# lamp.net
KiCad netlist of a schematic drawn in EAGLE
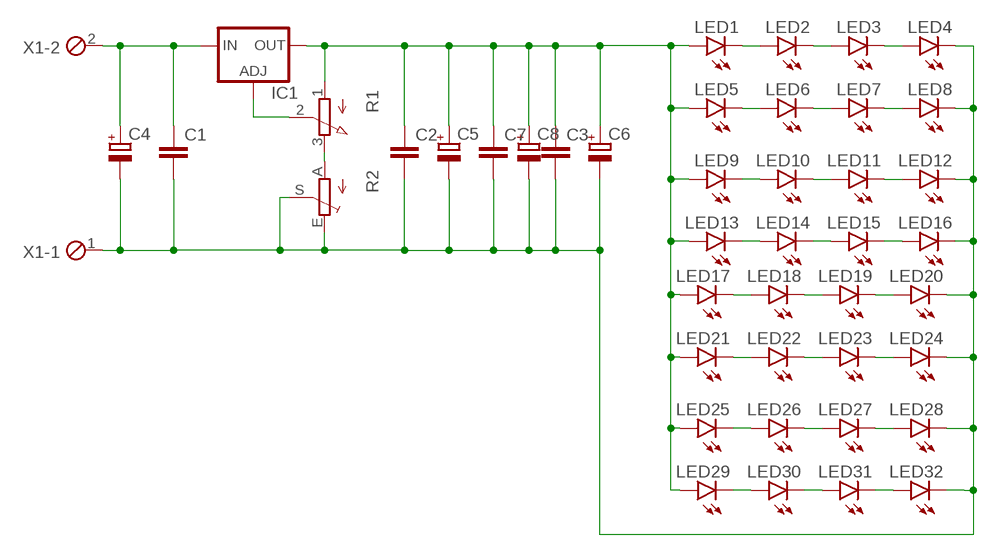
[diagram p0: schematic, sheet 1]

(export (version "E")
  (design (tool "Eeschema 10.0.6"))
  (components
    (comp (ref "C1")
      (value "C-EU025-025X050")
      (footprint "eagle-import:C025-025X050")
      (libsource (lib "eagle-import") (part "C-EU025-025X050"))
    )
    (comp (ref "C2")
      (value "C-EU025-025X050")
      (footprint "eagle-import:C025-025X050")
      (libsource (lib "eagle-import") (part "C-EU025-025X050"))
    )
    (comp (ref "C3")
      (value "C-EU025-025X050")
      (footprint "eagle-import:C025-025X050")
      (libsource (lib "eagle-import") (part "C-EU025-025X050"))
    )
    (comp (ref "C4")
      (value "CPOL-EUE2-5")
      (footprint "eagle-import:E2-5")
      (libsource (lib "eagle-import") (part "CPOL-EUE2-5"))
    )
    (comp (ref "C5")
      (value "CPOL-EUE2-5")
      (footprint "eagle-import:E2-5")
      (libsource (lib "eagle-import") (part "CPOL-EUE2-5"))
    )
    (comp (ref "C6")
      (value "CPOL-EUE2-5")
      (footprint "eagle-import:E2-5")
      (libsource (lib "eagle-import") (part "CPOL-EUE2-5"))
    )
    (comp (ref "C7")
      (value "C-EU025-025X050")
      (footprint "eagle-import:C025-025X050")
      (libsource (lib "eagle-import") (part "C-EU025-025X050"))
    )
    (comp (ref "C8")
      (value "CPOL-EUE2-5")
      (footprint "eagle-import:E2-5")
      (libsource (lib "eagle-import") (part "CPOL-EUE2-5"))
    )
    (comp (ref "IC1")
      (value "LM317TS")
      (footprint "eagle-import:317TS")
      (libsource (lib "eagle-import") (part "LM317TS"))
    )
    (comp (ref "LED1")
      (value "LED3MM")
      (footprint "eagle-import:LED3MM")
      (libsource (lib "eagle-import") (part "LED3MM"))
    )
    (comp (ref "LED2")
      (value "LED3MM")
      (footprint "eagle-import:LED3MM")
      (libsource (lib "eagle-import") (part "LED3MM"))
    )
    (comp (ref "LED3")
      (value "LED3MM")
      (footprint "eagle-import:LED3MM")
      (libsource (lib "eagle-import") (part "LED3MM"))
    )
    (comp (ref "LED4")
      (value "LED3MM")
      (footprint "eagle-import:LED3MM")
      (libsource (lib "eagle-import") (part "LED3MM"))
    )
    (comp (ref "LED5")
      (value "LED3MM")
      (footprint "eagle-import:LED3MM")
      (libsource (lib "eagle-import") (part "LED3MM"))
    )
    (comp (ref "LED6")
      (value "LED3MM")
      (footprint "eagle-import:LED3MM")
      (libsource (lib "eagle-import") (part "LED3MM"))
    )
    (comp (ref "LED7")
      (value "LED3MM")
      (footprint "eagle-import:LED3MM")
      (libsource (lib "eagle-import") (part "LED3MM"))
    )
    (comp (ref "LED8")
      (value "LED3MM")
      (footprint "eagle-import:LED3MM")
      (libsource (lib "eagle-import") (part "LED3MM"))
    )
    (comp (ref "LED9")
      (value "LED3MM")
      (footprint "eagle-import:LED3MM")
      (libsource (lib "eagle-import") (part "LED3MM"))
    )
    (comp (ref "LED10")
      (value "LED3MM")
      (footprint "eagle-import:LED3MM")
      (libsource (lib "eagle-import") (part "LED3MM"))
    )
    (comp (ref "LED11")
      (value "LED3MM")
      (footprint "eagle-import:LED3MM")
      (libsource (lib "eagle-import") (part "LED3MM"))
    )
    (comp (ref "LED12")
      (value "LED3MM")
      (footprint "eagle-import:LED3MM")
      (libsource (lib "eagle-import") (part "LED3MM"))
    )
    (comp (ref "LED13")
      (value "LED3MM")
      (footprint "eagle-import:LED3MM")
      (libsource (lib "eagle-import") (part "LED3MM"))
    )
    (comp (ref "LED14")
      (value "LED3MM")
      (footprint "eagle-import:LED3MM")
      (libsource (lib "eagle-import") (part "LED3MM"))
    )
    (comp (ref "LED15")
      (value "LED3MM")
      (footprint "eagle-import:LED3MM")
      (libsource (lib "eagle-import") (part "LED3MM"))
    )
    (comp (ref "LED16")
      (value "LED3MM")
      (footprint "eagle-import:LED3MM")
      (libsource (lib "eagle-import") (part "LED3MM"))
    )
    (comp (ref "LED17")
      (value "LED3MM")
      (footprint "eagle-import:LED3MM")
      (libsource (lib "eagle-import") (part "LED3MM"))
    )
    (comp (ref "LED18")
      (value "LED3MM")
      (footprint "eagle-import:LED3MM")
      (libsource (lib "eagle-import") (part "LED3MM"))
    )
    (comp (ref "LED19")
      (value "LED3MM")
      (footprint "eagle-import:LED3MM")
      (libsource (lib "eagle-import") (part "LED3MM"))
    )
    (comp (ref "LED20")
      (value "LED3MM")
      (footprint "eagle-import:LED3MM")
      (libsource (lib "eagle-import") (part "LED3MM"))
    )
    (comp (ref "LED21")
      (value "LED3MM")
      (footprint "eagle-import:LED3MM")
      (libsource (lib "eagle-import") (part "LED3MM"))
    )
    (comp (ref "LED22")
      (value "LED3MM")
      (footprint "eagle-import:LED3MM")
      (libsource (lib "eagle-import") (part "LED3MM"))
    )
    (comp (ref "LED23")
      (value "LED3MM")
      (footprint "eagle-import:LED3MM")
      (libsource (lib "eagle-import") (part "LED3MM"))
    )
    (comp (ref "LED24")
      (value "LED3MM")
      (footprint "eagle-import:LED3MM")
      (libsource (lib "eagle-import") (part "LED3MM"))
    )
    (comp (ref "LED25")
      (value "LED3MM")
      (footprint "eagle-import:LED3MM")
      (libsource (lib "eagle-import") (part "LED3MM"))
    )
    (comp (ref "LED26")
      (value "LED3MM")
      (footprint "eagle-import:LED3MM")
      (libsource (lib "eagle-import") (part "LED3MM"))
    )
    (comp (ref "LED27")
      (value "LED3MM")
      (footprint "eagle-import:LED3MM")
      (libsource (lib "eagle-import") (part "LED3MM"))
    )
    (comp (ref "LED28")
      (value "LED3MM")
      (footprint "eagle-import:LED3MM")
      (libsource (lib "eagle-import") (part "LED3MM"))
    )
    (comp (ref "LED29")
      (value "LED3MM")
      (footprint "eagle-import:LED3MM")
      (libsource (lib "eagle-import") (part "LED3MM"))
    )
    (comp (ref "LED30")
      (value "LED3MM")
      (footprint "eagle-import:LED3MM")
      (libsource (lib "eagle-import") (part "LED3MM"))
    )
    (comp (ref "LED31")
      (value "LED3MM")
      (footprint "eagle-import:LED3MM")
      (libsource (lib "eagle-import") (part "LED3MM"))
    )
    (comp (ref "LED32")
      (value "LED3MM")
      (footprint "eagle-import:LED3MM")
      (libsource (lib "eagle-import") (part "LED3MM"))
    )
    (comp (ref "R1")
      (value "3RP/1610N")
      (footprint "eagle-import:3RP_1610N")
      (libsource (lib "eagle-import") (part "3RP/1610N"))
    )
    (comp (ref "R2")
      (value "TRIM_EU-CA6V")
      (footprint "eagle-import:CA6V")
      (libsource (lib "eagle-import") (part "TRIM_EU-CA6V"))
    )
    (comp (ref "X1")
      (value "MPT2")
      (footprint "eagle-import:2POL254")
      (libsource (lib "eagle-import") (part "MPT2"))
    )
  )
  (nets
    (net (code "1") (name "Net-(IC1-ADJ)") (class "Default")
      (node (ref "IC1") (pin "1") (pinfunction "ADJ_1") (pintype "input"))
      (node (ref "R1") (pin "2") (pinfunction "S_2") (pintype "passive"))
    )
    (net (code "2") (name "Net-(IC1-IN)") (class "Default")
      (node (ref "C1") (pin "1") (pinfunction "1_1") (pintype "passive"))
      (node (ref "C4") (pin "+") (pinfunction "+_+") (pintype "passive"))
      (node (ref "IC1") (pin "3") (pinfunction "IN_3") (pintype "input"))
      (node (ref "X1") (pin "2") (pinfunction "1_2") (pintype "passive"))
    )
    (net (code "3") (name "Net-(IC1-OUT)") (class "Default")
      (node (ref "C2") (pin "1") (pinfunction "1_1") (pintype "passive"))
      (node (ref "C3") (pin "1") (pinfunction "1_1") (pintype "passive"))
      (node (ref "C5") (pin "+") (pinfunction "+_+") (pintype "passive"))
      (node (ref "C6") (pin "+") (pinfunction "+_+") (pintype "passive"))
      (node (ref "C7") (pin "1") (pinfunction "1_1") (pintype "passive"))
      (node (ref "C8") (pin "+") (pinfunction "+_+") (pintype "passive"))
      (node (ref "IC1") (pin "2") (pinfunction "OUT_2") (pintype "passive"))
      (node (ref "LED1") (pin "A") (pinfunction "A_A") (pintype "passive"))
      (node (ref "LED13") (pin "A") (pinfunction "A_A") (pintype "passive"))
      (node (ref "LED17") (pin "A") (pinfunction "A_A") (pintype "passive"))
      (node (ref "LED21") (pin "A") (pinfunction "A_A") (pintype "passive"))
      (node (ref "LED25") (pin "A") (pinfunction "A_A") (pintype "passive"))
      (node (ref "LED29") (pin "A") (pinfunction "A_A") (pintype "passive"))
      (node (ref "LED5") (pin "A") (pinfunction "A_A") (pintype "passive"))
      (node (ref "LED9") (pin "A") (pinfunction "A_A") (pintype "passive"))
      (node (ref "R1") (pin "1") (pinfunction "A_1") (pintype "passive"))
    )
    (net (code "4") (name "Net-(LED1-C)") (class "Default")
      (node (ref "LED1") (pin "K") (pinfunction "C_K") (pintype "passive"))
      (node (ref "LED2") (pin "A") (pinfunction "A_A") (pintype "passive"))
    )
    (net (code "5") (name "Net-(LED2-C)") (class "Default")
      (node (ref "LED2") (pin "K") (pinfunction "C_K") (pintype "passive"))
      (node (ref "LED3") (pin "A") (pinfunction "A_A") (pintype "passive"))
    )
    (net (code "6") (name "Net-(LED3-C)") (class "Default")
      (node (ref "LED3") (pin "K") (pinfunction "C_K") (pintype "passive"))
      (node (ref "LED4") (pin "A") (pinfunction "A_A") (pintype "passive"))
    )
    (net (code "7") (name "Net-(LED5-C)") (class "Default")
      (node (ref "LED5") (pin "K") (pinfunction "C_K") (pintype "passive"))
      (node (ref "LED6") (pin "A") (pinfunction "A_A") (pintype "passive"))
    )
    (net (code "8") (name "Net-(LED6-C)") (class "Default")
      (node (ref "LED6") (pin "K") (pinfunction "C_K") (pintype "passive"))
      (node (ref "LED7") (pin "A") (pinfunction "A_A") (pintype "passive"))
    )
    (net (code "9") (name "Net-(LED7-C)") (class "Default")
      (node (ref "LED7") (pin "K") (pinfunction "C_K") (pintype "passive"))
      (node (ref "LED8") (pin "A") (pinfunction "A_A") (pintype "passive"))
    )
    (net (code "10") (name "Net-(LED9-C)") (class "Default")
      (node (ref "LED10") (pin "A") (pinfunction "A_A") (pintype "passive"))
      (node (ref "LED9") (pin "K") (pinfunction "C_K") (pintype "passive"))
    )
    (net (code "11") (name "Net-(LED10-C)") (class "Default")
      (node (ref "LED10") (pin "K") (pinfunction "C_K") (pintype "passive"))
      (node (ref "LED11") (pin "A") (pinfunction "A_A") (pintype "passive"))
    )
    (net (code "12") (name "Net-(LED11-C)") (class "Default")
      (node (ref "LED11") (pin "K") (pinfunction "C_K") (pintype "passive"))
      (node (ref "LED12") (pin "A") (pinfunction "A_A") (pintype "passive"))
    )
    (net (code "13") (name "Net-(LED12-C)") (class "Default")
      (node (ref "C1") (pin "2") (pinfunction "2_2") (pintype "passive"))
      (node (ref "C2") (pin "2") (pinfunction "2_2") (pintype "passive"))
      (node (ref "C3") (pin "2") (pinfunction "2_2") (pintype "passive"))
      (node (ref "C4") (pin "-") (pinfunction "-_-") (pintype "passive"))
      (node (ref "C5") (pin "-") (pinfunction "-_-") (pintype "passive"))
      (node (ref "C6") (pin "-") (pinfunction "-_-") (pintype "passive"))
      (node (ref "C7") (pin "2") (pinfunction "2_2") (pintype "passive"))
      (node (ref "C8") (pin "-") (pinfunction "-_-") (pintype "passive"))
      (node (ref "LED12") (pin "K") (pinfunction "C_K") (pintype "passive"))
      (node (ref "LED16") (pin "K") (pinfunction "C_K") (pintype "passive"))
      (node (ref "LED20") (pin "K") (pinfunction "C_K") (pintype "passive"))
      (node (ref "LED24") (pin "K") (pinfunction "C_K") (pintype "passive"))
      (node (ref "LED28") (pin "K") (pinfunction "C_K") (pintype "passive"))
      (node (ref "LED32") (pin "K") (pinfunction "C_K") (pintype "passive"))
      (node (ref "LED4") (pin "K") (pinfunction "C_K") (pintype "passive"))
      (node (ref "LED8") (pin "K") (pinfunction "C_K") (pintype "passive"))
      (node (ref "R2") (pin "E") (pinfunction "E_E") (pintype "passive"))
      (node (ref "R2") (pin "S") (pinfunction "S_S") (pintype "passive"))
      (node (ref "X1") (pin "1") (pinfunction "1_1") (pintype "passive"))
    )
    (net (code "14") (name "Net-(LED13-C)") (class "Default")
      (node (ref "LED13") (pin "K") (pinfunction "C_K") (pintype "passive"))
      (node (ref "LED14") (pin "A") (pinfunction "A_A") (pintype "passive"))
    )
    (net (code "15") (name "Net-(LED14-C)") (class "Default")
      (node (ref "LED14") (pin "K") (pinfunction "C_K") (pintype "passive"))
      (node (ref "LED15") (pin "A") (pinfunction "A_A") (pintype "passive"))
    )
    (net (code "16") (name "Net-(LED15-C)") (class "Default")
      (node (ref "LED15") (pin "K") (pinfunction "C_K") (pintype "passive"))
      (node (ref "LED16") (pin "A") (pinfunction "A_A") (pintype "passive"))
    )
    (net (code "17") (name "Net-(LED17-C)") (class "Default")
      (node (ref "LED17") (pin "K") (pinfunction "C_K") (pintype "passive"))
      (node (ref "LED18") (pin "A") (pinfunction "A_A") (pintype "passive"))
    )
    (net (code "18") (name "Net-(LED18-C)") (class "Default")
      (node (ref "LED18") (pin "K") (pinfunction "C_K") (pintype "passive"))
      (node (ref "LED19") (pin "A") (pinfunction "A_A") (pintype "passive"))
    )
    (net (code "19") (name "Net-(LED19-C)") (class "Default")
      (node (ref "LED19") (pin "K") (pinfunction "C_K") (pintype "passive"))
      (node (ref "LED20") (pin "A") (pinfunction "A_A") (pintype "passive"))
    )
    (net (code "20") (name "Net-(LED21-C)") (class "Default")
      (node (ref "LED21") (pin "K") (pinfunction "C_K") (pintype "passive"))
      (node (ref "LED22") (pin "A") (pinfunction "A_A") (pintype "passive"))
    )
    (net (code "21") (name "Net-(LED22-C)") (class "Default")
      (node (ref "LED22") (pin "K") (pinfunction "C_K") (pintype "passive"))
      (node (ref "LED23") (pin "A") (pinfunction "A_A") (pintype "passive"))
    )
    (net (code "22") (name "Net-(LED23-C)") (class "Default")
      (node (ref "LED23") (pin "K") (pinfunction "C_K") (pintype "passive"))
      (node (ref "LED24") (pin "A") (pinfunction "A_A") (pintype "passive"))
    )
    (net (code "23") (name "Net-(LED25-C)") (class "Default")
      (node (ref "LED25") (pin "K") (pinfunction "C_K") (pintype "passive"))
      (node (ref "LED26") (pin "A") (pinfunction "A_A") (pintype "passive"))
    )
    (net (code "24") (name "Net-(LED26-C)") (class "Default")
      (node (ref "LED26") (pin "K") (pinfunction "C_K") (pintype "passive"))
      (node (ref "LED27") (pin "A") (pinfunction "A_A") (pintype "passive"))
    )
    (net (code "25") (name "Net-(LED27-C)") (class "Default")
      (node (ref "LED27") (pin "K") (pinfunction "C_K") (pintype "passive"))
      (node (ref "LED28") (pin "A") (pinfunction "A_A") (pintype "passive"))
    )
    (net (code "26") (name "Net-(LED29-C)") (class "Default")
      (node (ref "LED29") (pin "K") (pinfunction "C_K") (pintype "passive"))
      (node (ref "LED30") (pin "A") (pinfunction "A_A") (pintype "passive"))
    )
    (net (code "27") (name "Net-(LED30-C)") (class "Default")
      (node (ref "LED30") (pin "K") (pinfunction "C_K") (pintype "passive"))
      (node (ref "LED31") (pin "A") (pinfunction "A_A") (pintype "passive"))
    )
    (net (code "28") (name "Net-(LED31-C)") (class "Default")
      (node (ref "LED31") (pin "K") (pinfunction "C_K") (pintype "passive"))
      (node (ref "LED32") (pin "A") (pinfunction "A_A") (pintype "passive"))
    )
    (net (code "29") (name "Net-(R1-E)") (class "Default")
      (node (ref "R1") (pin "3") (pinfunction "E_3") (pintype "passive"))
      (node (ref "R2") (pin "A") (pinfunction "A_A") (pintype "passive"))
    )
  )
)
